# io-board_rackmount.net
KiCad netlist of a schematic drawn in EAGLE
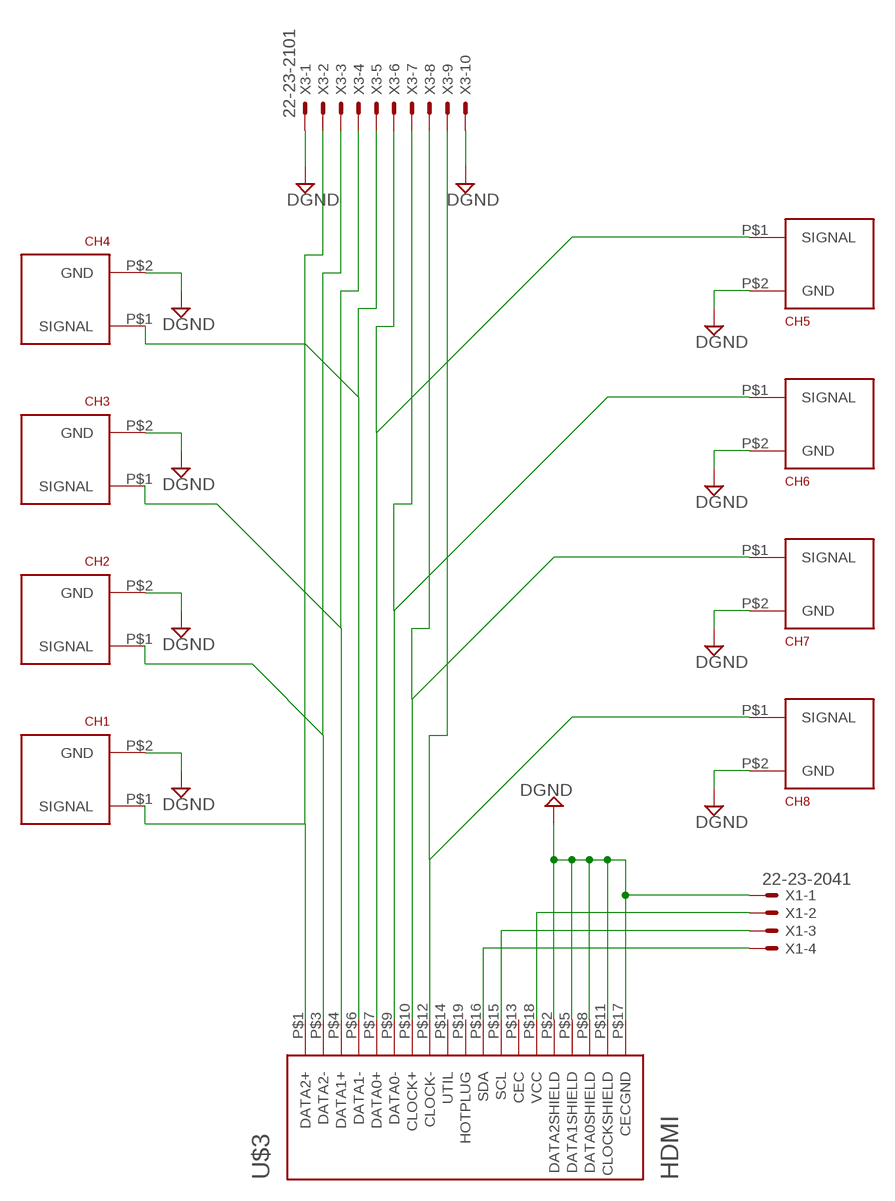
[diagram p0: schematic, sheet 1]

(export (version "E")
  (design (tool "Eeschema 10.0.6"))
  (components
    (comp (ref "CH1")
      (value "BNC_VERTICAL")
      (footprint "eagle-import:BNC_VERTICAL")
      (libsource (lib "eagle-import") (part "BNC_VERTICAL"))
    )
    (comp (ref "CH2")
      (value "BNC_VERTICAL")
      (footprint "eagle-import:BNC_VERTICAL")
      (libsource (lib "eagle-import") (part "BNC_VERTICAL"))
    )
    (comp (ref "CH3")
      (value "BNC_VERTICAL")
      (footprint "eagle-import:BNC_VERTICAL")
      (libsource (lib "eagle-import") (part "BNC_VERTICAL"))
    )
    (comp (ref "CH4")
      (value "BNC_VERTICAL")
      (footprint "eagle-import:BNC_VERTICAL")
      (libsource (lib "eagle-import") (part "BNC_VERTICAL"))
    )
    (comp (ref "CH5")
      (value "BNC_VERTICAL")
      (footprint "eagle-import:BNC_VERTICAL")
      (libsource (lib "eagle-import") (part "BNC_VERTICAL"))
    )
    (comp (ref "CH6")
      (value "BNC_VERTICAL")
      (footprint "eagle-import:BNC_VERTICAL")
      (libsource (lib "eagle-import") (part "BNC_VERTICAL"))
    )
    (comp (ref "CH7")
      (value "BNC_VERTICAL")
      (footprint "eagle-import:BNC_VERTICAL")
      (libsource (lib "eagle-import") (part "BNC_VERTICAL"))
    )
    (comp (ref "CH8")
      (value "BNC_VERTICAL")
      (footprint "eagle-import:BNC_VERTICAL")
      (libsource (lib "eagle-import") (part "BNC_VERTICAL"))
    )
    (comp (ref "U$3")
      (value "HDMI")
      (footprint "eagle-import:HDMI_A")
      (libsource (lib "eagle-import") (part "HDMI"))
    )
    (comp (ref "X1")
      (value "22-23-2041")
      (footprint "eagle-import:22-23-2041")
      (fields (field (name "MF") "MOLEX"))
      (libsource (lib "eagle-import") (part "22-23-2041"))
    )
    (comp (ref "X3")
      (value "22-23-2101")
      (footprint "eagle-import:22-23-2101")
      (fields (field (name "MF") "MOLEX"))
      (libsource (lib "eagle-import") (part "22-23-2101"))
    )
  )
  (nets
    (net (code "1") (name "DGND") (class "Default")
      (node (ref "CH1") (pin "P$2") (pinfunction "GND_P$2") (pintype "bidirectional"))
      (node (ref "CH2") (pin "P$2") (pinfunction "GND_P$2") (pintype "bidirectional"))
      (node (ref "CH3") (pin "P$2") (pinfunction "GND_P$2") (pintype "bidirectional"))
      (node (ref "CH4") (pin "P$2") (pinfunction "GND_P$2") (pintype "bidirectional"))
      (node (ref "CH5") (pin "P$2") (pinfunction "GND_P$2") (pintype "bidirectional"))
      (node (ref "CH6") (pin "P$2") (pinfunction "GND_P$2") (pintype "bidirectional"))
      (node (ref "CH7") (pin "P$2") (pinfunction "GND_P$2") (pintype "bidirectional"))
      (node (ref "CH8") (pin "P$2") (pinfunction "GND_P$2") (pintype "bidirectional"))
      (node (ref "U$3") (pin "P$11") (pinfunction "CLOCKSHIELD_P$11") (pintype "bidirectional"))
      (node (ref "U$3") (pin "P$17") (pinfunction "CECGND_P$17") (pintype "bidirectional"))
      (node (ref "U$3") (pin "P$2") (pinfunction "DATA2SHIELD_P$2") (pintype "bidirectional"))
      (node (ref "U$3") (pin "P$5") (pinfunction "DATA1SHIELD_P$5") (pintype "bidirectional"))
      (node (ref "U$3") (pin "P$8") (pinfunction "DATA0SHIELD_P$8") (pintype "bidirectional"))
      (node (ref "X1") (pin "1") (pinfunction "S_1") (pintype "passive"))
      (node (ref "X3") (pin "1") (pinfunction "S_1") (pintype "passive"))
      (node (ref "X3") (pin "10") (pinfunction "S_10") (pintype "passive"))
    )
    (net (code "2") (name "Net-(CH1-SIGNAL)") (class "Default")
      (node (ref "CH1") (pin "P$1") (pinfunction "SIGNAL_P$1") (pintype "bidirectional"))
      (node (ref "U$3") (pin "P$1") (pinfunction "DATA2+_P$1") (pintype "bidirectional"))
      (node (ref "X3") (pin "2") (pinfunction "S_2") (pintype "passive"))
    )
    (net (code "3") (name "Net-(CH2-SIGNAL)") (class "Default")
      (node (ref "CH2") (pin "P$1") (pinfunction "SIGNAL_P$1") (pintype "bidirectional"))
      (node (ref "U$3") (pin "P$3") (pinfunction "DATA2-_P$3") (pintype "bidirectional"))
      (node (ref "X3") (pin "3") (pinfunction "S_3") (pintype "passive"))
    )
    (net (code "4") (name "Net-(CH3-SIGNAL)") (class "Default")
      (node (ref "CH3") (pin "P$1") (pinfunction "SIGNAL_P$1") (pintype "bidirectional"))
      (node (ref "U$3") (pin "P$4") (pinfunction "DATA1+_P$4") (pintype "bidirectional"))
      (node (ref "X3") (pin "4") (pinfunction "S_4") (pintype "passive"))
    )
    (net (code "5") (name "Net-(CH4-SIGNAL)") (class "Default")
      (node (ref "CH4") (pin "P$1") (pinfunction "SIGNAL_P$1") (pintype "bidirectional"))
      (node (ref "U$3") (pin "P$6") (pinfunction "DATA1-_P$6") (pintype "bidirectional"))
      (node (ref "X3") (pin "5") (pinfunction "S_5") (pintype "passive"))
    )
    (net (code "6") (name "Net-(CH5-SIGNAL)") (class "Default")
      (node (ref "CH5") (pin "P$1") (pinfunction "SIGNAL_P$1") (pintype "bidirectional"))
      (node (ref "U$3") (pin "P$7") (pinfunction "DATA0+_P$7") (pintype "bidirectional"))
      (node (ref "X3") (pin "6") (pinfunction "S_6") (pintype "passive"))
    )
    (net (code "7") (name "Net-(CH6-SIGNAL)") (class "Default")
      (node (ref "CH6") (pin "P$1") (pinfunction "SIGNAL_P$1") (pintype "bidirectional"))
      (node (ref "U$3") (pin "P$9") (pinfunction "DATA0-_P$9") (pintype "bidirectional"))
      (node (ref "X3") (pin "7") (pinfunction "S_7") (pintype "passive"))
    )
    (net (code "8") (name "Net-(CH7-SIGNAL)") (class "Default")
      (node (ref "CH7") (pin "P$1") (pinfunction "SIGNAL_P$1") (pintype "bidirectional"))
      (node (ref "U$3") (pin "P$10") (pinfunction "CLOCK+_P$10") (pintype "bidirectional"))
      (node (ref "X3") (pin "8") (pinfunction "S_8") (pintype "passive"))
    )
    (net (code "9") (name "Net-(CH8-SIGNAL)") (class "Default")
      (node (ref "CH8") (pin "P$1") (pinfunction "SIGNAL_P$1") (pintype "bidirectional"))
      (node (ref "U$3") (pin "P$12") (pinfunction "CLOCK-_P$12") (pintype "bidirectional"))
      (node (ref "X3") (pin "9") (pinfunction "S_9") (pintype "passive"))
    )
    (net (code "10") (name "Net-(U$3-SCL)") (class "Default")
      (node (ref "U$3") (pin "P$15") (pinfunction "SCL_P$15") (pintype "bidirectional"))
      (node (ref "X1") (pin "3") (pinfunction "S_3") (pintype "passive"))
    )
    (net (code "11") (name "Net-(U$3-SDA)") (class "Default")
      (node (ref "U$3") (pin "P$16") (pinfunction "SDA_P$16") (pintype "bidirectional"))
      (node (ref "X1") (pin "4") (pinfunction "S_4") (pintype "passive"))
    )
    (net (code "12") (name "Net-(U$3-VCC)") (class "Default")
      (node (ref "U$3") (pin "P$18") (pinfunction "VCC_P$18") (pintype "bidirectional"))
      (node (ref "X1") (pin "2") (pinfunction "S_2") (pintype "passive"))
    )
    (net (code "13") (name "unconnected-(U$3-CEC-PadP$13)") (class "Default")
      (node (ref "U$3") (pin "P$13") (pinfunction "CEC_P$13") (pintype "bidirectional"))
    )
    (net (code "14") (name "unconnected-(U$3-HOTPLUG-PadP$19)") (class "Default")
      (node (ref "U$3") (pin "P$19") (pinfunction "HOTPLUG_P$19") (pintype "bidirectional"))
    )
    (net (code "15") (name "unconnected-(U$3-UTIL-PadP$14)") (class "Default")
      (node (ref "U$3") (pin "P$14") (pinfunction "UTIL_P$14") (pintype "bidirectional"))
    )
  )
)
